# Sheet2.net
KiCad netlist of a schematic drawn in Altium Designer
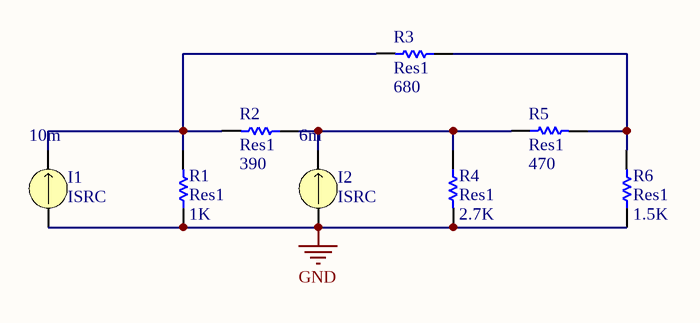
[diagram p0: Sheet2.SchDoc]

(export (version "E")
  (design (tool "Eeschema 10.0.6"))
  (components
    (comp (ref "I1")
      (value "ISRC")
      (description "Current Source")
      (fields (field (name "ALTIUM_VALUE") "10m") (field (name "PUBLISHER") "Altium Limited"))
      (libsource (lib "Simulation Sources") (part "ISRC"))
    )
    (comp (ref "I2")
      (value "ISRC")
      (description "Current Source")
      (fields (field (name "ALTIUM_VALUE") "6m") (field (name "PUBLISHER") "Altium Limited"))
      (libsource (lib "Simulation Sources") (part "ISRC"))
    )
    (comp (ref "R1")
      (value "Res1")
      (footprint "AXIAL-0.3")
      (description "Resistor")
      (fields (field (name "ALTIUM_VALUE") "1K") (field (name "PUBLISHER") "Altium Limited"))
      (libsource (lib "Miscellaneous Devices") (part "Res1"))
    )
    (comp (ref "R2")
      (value "Res1")
      (footprint "AXIAL-0.3")
      (description "Resistor")
      (fields (field (name "ALTIUM_VALUE") "390") (field (name "PUBLISHER") "Altium Limited"))
      (libsource (lib "Miscellaneous Devices") (part "Res1"))
    )
    (comp (ref "R3")
      (value "Res1")
      (footprint "AXIAL-0.3")
      (description "Resistor")
      (fields (field (name "ALTIUM_VALUE") "680") (field (name "PUBLISHER") "Altium Limited"))
      (libsource (lib "Miscellaneous Devices") (part "Res1"))
    )
    (comp (ref "R4")
      (value "Res1")
      (footprint "AXIAL-0.3")
      (description "Resistor")
      (fields (field (name "ALTIUM_VALUE") "2.7K") (field (name "PUBLISHER") "Altium Limited"))
      (libsource (lib "Miscellaneous Devices") (part "Res1"))
    )
    (comp (ref "R5")
      (value "Res1")
      (footprint "AXIAL-0.3")
      (description "Resistor")
      (fields (field (name "ALTIUM_VALUE") "470") (field (name "PUBLISHER") "Altium Limited"))
      (libsource (lib "Miscellaneous Devices") (part "Res1"))
    )
    (comp (ref "R6")
      (value "Res1")
      (footprint "AXIAL-0.3")
      (description "Resistor")
      (fields (field (name "ALTIUM_VALUE") "1.5K") (field (name "PUBLISHER") "Altium Limited"))
      (libsource (lib "Miscellaneous Devices") (part "Res1"))
    )
  )
  (nets
    (net (code "1") (name "GND") (class "Default")
      (node (ref "I1") (pin "1") (pinfunction "1_1") (pintype "passive"))
      (node (ref "I2") (pin "1") (pinfunction "1_1") (pintype "passive"))
      (node (ref "R1") (pin "1") (pinfunction "1_1") (pintype "passive"))
      (node (ref "R4") (pin "2") (pinfunction "2_2") (pintype "passive"))
      (node (ref "R6") (pin "1") (pinfunction "1_1") (pintype "passive"))
    )
    (net (code "2") (name "Net-(I1-Pad2)") (class "Default")
      (node (ref "I1") (pin "2") (pinfunction "2_2") (pintype "passive"))
      (node (ref "R1") (pin "2") (pinfunction "2_2") (pintype "passive"))
      (node (ref "R2") (pin "2") (pinfunction "2_2") (pintype "passive"))
      (node (ref "R3") (pin "2") (pinfunction "2_2") (pintype "passive"))
    )
    (net (code "3") (name "Net-(I2-Pad2)") (class "Default")
      (node (ref "I2") (pin "2") (pinfunction "2_2") (pintype "passive"))
      (node (ref "R2") (pin "1") (pinfunction "1_1") (pintype "passive"))
      (node (ref "R4") (pin "1") (pinfunction "1_1") (pintype "passive"))
      (node (ref "R5") (pin "1") (pinfunction "1_1") (pintype "passive"))
    )
    (net (code "4") (name "Net-(R3-Pad1)") (class "Default")
      (node (ref "R3") (pin "1") (pinfunction "1_1") (pintype "passive"))
      (node (ref "R5") (pin "2") (pinfunction "2_2") (pintype "passive"))
      (node (ref "R6") (pin "2") (pinfunction "2_2") (pintype "passive"))
    )
  )
)
